# connectors.net
KiCad netlist of a schematic drawn in Altium Designer
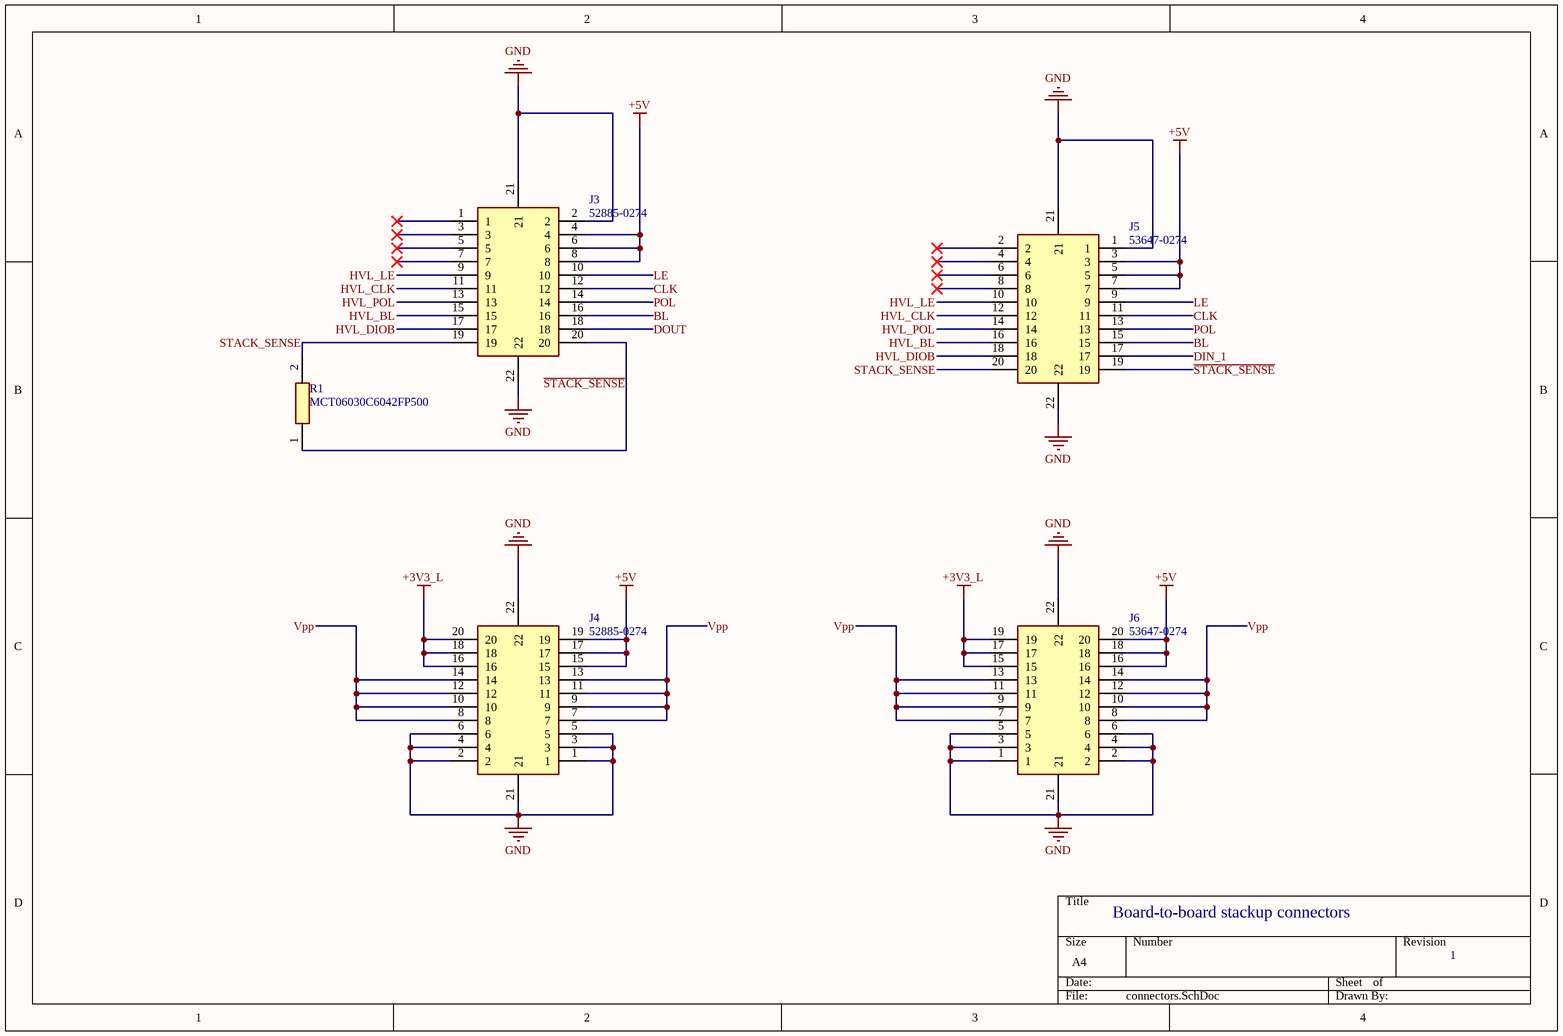
[diagram p0: connectors.SchDoc]

(export (version "E")
  (design (tool "Eeschema 10.0.6"))
  (components
    (comp (ref "J3")
      (value "52885-0274")
      (footprint "SamacSys:528850274")
      (description "Connector")
      (fields (field (name "MOUSER PART NUMBER") "538-52885-0274"))
      (libsource (lib "*") (part "52885-0274"))
    )
    (comp (ref "J4")
      (value "52885-0274")
      (footprint "SamacSys:528850274")
      (description "Connector")
      (fields (field (name "MOUSER PART NUMBER") "538-52885-0274"))
      (libsource (lib "") (part "52885-0274_1"))
    )
    (comp (ref "J5")
      (value "53647-0274")
      (footprint "SamacSys:536470274")
      (description "Connector")
      (fields (field (name "MOUSER PART NUMBER") "538-53647-0274"))
      (libsource (lib "*") (part "53647-0274"))
    )
    (comp (ref "J6")
      (value "53647-0274")
      (footprint "SamacSys:536470274")
      (description "Connector")
      (fields (field (name "MOUSER PART NUMBER") "538-53647-0274"))
      (libsource (lib "") (part "53647-0274_1"))
    )
    (comp (ref "R1")
      (value "MCT06030C6042FP500")
      (footprint "SamacSys:RESC1608X55N")
      (description "Resistor")
      (libsource (lib "*") (part "MCT06030C6042FP500"))
    )
  )
  (nets
    (net (code "1") (name "+3V3_L") (class "Default")
      (node (ref "J4") (pin "16") (pinfunction "16_16") (pintype "passive"))
      (node (ref "J4") (pin "18") (pinfunction "18_18") (pintype "passive"))
      (node (ref "J4") (pin "20") (pinfunction "20_20") (pintype "passive"))
      (node (ref "J6") (pin "15") (pinfunction "15_15") (pintype "passive"))
      (node (ref "J6") (pin "17") (pinfunction "17_17") (pintype "passive"))
      (node (ref "J6") (pin "19") (pinfunction "19_19") (pintype "passive"))
    )
    (net (code "2") (name "+5V") (class "Default")
      (node (ref "J3") (pin "4") (pinfunction "4_4") (pintype "passive"))
      (node (ref "J3") (pin "6") (pinfunction "6_6") (pintype "passive"))
      (node (ref "J3") (pin "8") (pinfunction "8_8") (pintype "passive"))
      (node (ref "J4") (pin "15") (pinfunction "15_15") (pintype "passive"))
      (node (ref "J4") (pin "17") (pinfunction "17_17") (pintype "passive"))
      (node (ref "J4") (pin "19") (pinfunction "19_19") (pintype "passive"))
      (node (ref "J5") (pin "3") (pinfunction "3_3") (pintype "passive"))
      (node (ref "J5") (pin "5") (pinfunction "5_5") (pintype "passive"))
      (node (ref "J5") (pin "7") (pinfunction "7_7") (pintype "passive"))
      (node (ref "J6") (pin "16") (pinfunction "16_16") (pintype "passive"))
      (node (ref "J6") (pin "18") (pinfunction "18_18") (pintype "passive"))
      (node (ref "J6") (pin "20") (pinfunction "20_20") (pintype "passive"))
    )
    (net (code "3") (name "/BL") (class "Default")
      (node (ref "J3") (pin "16") (pinfunction "16_16") (pintype "passive"))
      (node (ref "J5") (pin "15") (pinfunction "15_15") (pintype "passive"))
    )
    (net (code "4") (name "/CLK") (class "Default")
      (node (ref "J3") (pin "12") (pinfunction "12_12") (pintype "passive"))
      (node (ref "J5") (pin "11") (pinfunction "11_11") (pintype "passive"))
    )
    (net (code "5") (name "/DIN_1") (class "Default")
      (node (ref "J5") (pin "17") (pinfunction "17_17") (pintype "passive"))
    )
    (net (code "6") (name "/DOUT") (class "Default")
      (node (ref "J3") (pin "18") (pinfunction "18_18") (pintype "passive"))
    )
    (net (code "7") (name "/HVL_BL") (class "Default")
      (node (ref "J3") (pin "15") (pinfunction "15_15") (pintype "passive"))
      (node (ref "J5") (pin "16") (pinfunction "16_16") (pintype "passive"))
    )
    (net (code "8") (name "/HVL_CLK") (class "Default")
      (node (ref "J3") (pin "11") (pinfunction "11_11") (pintype "passive"))
      (node (ref "J5") (pin "12") (pinfunction "12_12") (pintype "passive"))
    )
    (net (code "9") (name "/HVL_DIOB") (class "Default")
      (node (ref "J3") (pin "17") (pinfunction "17_17") (pintype "passive"))
      (node (ref "J5") (pin "18") (pinfunction "18_18") (pintype "passive"))
    )
    (net (code "10") (name "/HVL_LE") (class "Default")
      (node (ref "J3") (pin "9") (pinfunction "9_9") (pintype "passive"))
      (node (ref "J5") (pin "10") (pinfunction "10_10") (pintype "passive"))
    )
    (net (code "11") (name "/HVL_POL") (class "Default")
      (node (ref "J3") (pin "13") (pinfunction "13_13") (pintype "passive"))
      (node (ref "J5") (pin "14") (pinfunction "14_14") (pintype "passive"))
    )
    (net (code "12") (name "/LE") (class "Default")
      (node (ref "J3") (pin "10") (pinfunction "10_10") (pintype "passive"))
      (node (ref "J5") (pin "9") (pinfunction "9_9") (pintype "passive"))
    )
    (net (code "13") (name "/POL") (class "Default")
      (node (ref "J3") (pin "14") (pinfunction "14_14") (pintype "passive"))
      (node (ref "J5") (pin "13") (pinfunction "13_13") (pintype "passive"))
    )
    (net (code "14") (name "/STACK_SENSE") (class "Default")
      (node (ref "J3") (pin "19") (pinfunction "19_19") (pintype "passive"))
      (node (ref "J5") (pin "20") (pinfunction "20_20") (pintype "passive"))
      (node (ref "R1") (pin "2") (pinfunction "2_2") (pintype "passive"))
    )
    (net (code "15") (name "/Vpp") (class "Default")
      (node (ref "J4") (pin "10") (pinfunction "10_10") (pintype "passive"))
      (node (ref "J4") (pin "11") (pinfunction "11_11") (pintype "passive"))
      (node (ref "J4") (pin "12") (pinfunction "12_12") (pintype "passive"))
      (node (ref "J4") (pin "13") (pinfunction "13_13") (pintype "passive"))
      (node (ref "J4") (pin "14") (pinfunction "14_14") (pintype "passive"))
      (node (ref "J4") (pin "7") (pinfunction "7_7") (pintype "passive"))
      (node (ref "J4") (pin "8") (pinfunction "8_8") (pintype "passive"))
      (node (ref "J4") (pin "9") (pinfunction "9_9") (pintype "passive"))
      (node (ref "J6") (pin "10") (pinfunction "10_10") (pintype "passive"))
      (node (ref "J6") (pin "11") (pinfunction "11_11") (pintype "passive"))
      (node (ref "J6") (pin "12") (pinfunction "12_12") (pintype "passive"))
      (node (ref "J6") (pin "13") (pinfunction "13_13") (pintype "passive"))
      (node (ref "J6") (pin "14") (pinfunction "14_14") (pintype "passive"))
      (node (ref "J6") (pin "7") (pinfunction "7_7") (pintype "passive"))
      (node (ref "J6") (pin "8") (pinfunction "8_8") (pintype "passive"))
      (node (ref "J6") (pin "9") (pinfunction "9_9") (pintype "passive"))
    )
    (net (code "16") (name "/~{STACK_SENSE}") (class "Default")
      (node (ref "J3") (pin "20") (pinfunction "20_20") (pintype "passive"))
      (node (ref "J5") (pin "19") (pinfunction "19_19") (pintype "passive"))
      (node (ref "R1") (pin "1") (pinfunction "1_1") (pintype "passive"))
    )
    (net (code "17") (name "GND") (class "Default")
      (node (ref "J3") (pin "2") (pinfunction "2_2") (pintype "passive"))
      (node (ref "J3") (pin "21") (pinfunction "21_21") (pintype "passive"))
      (node (ref "J3") (pin "22") (pinfunction "22_22") (pintype "passive"))
      (node (ref "J4") (pin "1") (pinfunction "1_1") (pintype "passive"))
      (node (ref "J4") (pin "2") (pinfunction "2_2") (pintype "passive"))
      (node (ref "J4") (pin "21") (pinfunction "21_21") (pintype "passive"))
      (node (ref "J4") (pin "22") (pinfunction "22_22") (pintype "passive"))
      (node (ref "J4") (pin "3") (pinfunction "3_3") (pintype "passive"))
      (node (ref "J4") (pin "4") (pinfunction "4_4") (pintype "passive"))
      (node (ref "J4") (pin "5") (pinfunction "5_5") (pintype "passive"))
      (node (ref "J4") (pin "6") (pinfunction "6_6") (pintype "passive"))
      (node (ref "J5") (pin "1") (pinfunction "1_1") (pintype "passive"))
      (node (ref "J5") (pin "21") (pinfunction "21_21") (pintype "passive"))
      (node (ref "J5") (pin "22") (pinfunction "22_22") (pintype "passive"))
      (node (ref "J6") (pin "1") (pinfunction "1_1") (pintype "passive"))
      (node (ref "J6") (pin "2") (pinfunction "2_2") (pintype "passive"))
      (node (ref "J6") (pin "21") (pinfunction "21_21") (pintype "passive"))
      (node (ref "J6") (pin "22") (pinfunction "22_22") (pintype "passive"))
      (node (ref "J6") (pin "3") (pinfunction "3_3") (pintype "passive"))
      (node (ref "J6") (pin "4") (pinfunction "4_4") (pintype "passive"))
      (node (ref "J6") (pin "5") (pinfunction "5_5") (pintype "passive"))
      (node (ref "J6") (pin "6") (pinfunction "6_6") (pintype "passive"))
    )
    (net (code "18") (name "unconnected-(J3-Pad1)") (class "Default")
      (node (ref "J3") (pin "1") (pinfunction "1_1") (pintype "passive+no_connect"))
    )
    (net (code "19") (name "unconnected-(J3-Pad3)") (class "Default")
      (node (ref "J3") (pin "3") (pinfunction "3_3") (pintype "passive+no_connect"))
    )
    (net (code "20") (name "unconnected-(J3-Pad5)") (class "Default")
      (node (ref "J3") (pin "5") (pinfunction "5_5") (pintype "passive+no_connect"))
    )
    (net (code "21") (name "unconnected-(J3-Pad7)") (class "Default")
      (node (ref "J3") (pin "7") (pinfunction "7_7") (pintype "passive+no_connect"))
    )
    (net (code "22") (name "unconnected-(J5-Pad2)") (class "Default")
      (node (ref "J5") (pin "2") (pinfunction "2_2") (pintype "passive+no_connect"))
    )
    (net (code "23") (name "unconnected-(J5-Pad4)") (class "Default")
      (node (ref "J5") (pin "4") (pinfunction "4_4") (pintype "passive+no_connect"))
    )
    (net (code "24") (name "unconnected-(J5-Pad6)") (class "Default")
      (node (ref "J5") (pin "6") (pinfunction "6_6") (pintype "passive+no_connect"))
    )
    (net (code "25") (name "unconnected-(J5-Pad8)") (class "Default")
      (node (ref "J5") (pin "8") (pinfunction "8_8") (pintype "passive+no_connect"))
    )
  )
)
